# INA219-SOT23.net
KiCad netlist of a schematic drawn in EAGLE
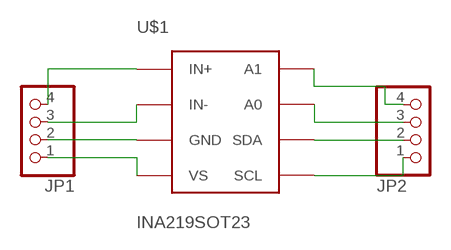
[diagram p0: schematic, sheet 1]

(export (version "E")
  (design (tool "Eeschema 10.0.6"))
  (components
    (comp (ref "JP1")
      (value "PINHD-1X4")
      (footprint "eagle-import:1X04")
      (libsource (lib "eagle-import") (part "PINHD-1X4"))
    )
    (comp (ref "JP2")
      (value "PINHD-1X4")
      (footprint "eagle-import:1X04")
      (libsource (lib "eagle-import") (part "PINHD-1X4"))
    )
    (comp (ref "U$1")
      (value "INA219SOT23")
      (footprint "eagle-import:SOT-23-8")
      (libsource (lib "eagle-import") (part "INA219SOT23"))
    )
  )
  (nets
    (net (code "1") (name "Net-(U$1-A0)") (class "Default")
      (node (ref "JP2") (pin "3") (pinfunction "3_3") (pintype "passive"))
      (node (ref "U$1") (pin "P$7") (pinfunction "A0_P$7") (pintype "bidirectional"))
    )
    (net (code "2") (name "Net-(U$1-A1)") (class "Default")
      (node (ref "JP2") (pin "4") (pinfunction "4_4") (pintype "passive"))
      (node (ref "U$1") (pin "P$8") (pinfunction "A1_P$8") (pintype "bidirectional"))
    )
    (net (code "3") (name "Net-(U$1-GND)") (class "Default")
      (node (ref "JP1") (pin "2") (pinfunction "2_2") (pintype "passive"))
      (node (ref "U$1") (pin "P$3") (pinfunction "GND_P$3") (pintype "bidirectional"))
    )
    (net (code "4") (name "Net-(U$1-IN+)") (class "Default")
      (node (ref "JP1") (pin "4") (pinfunction "4_4") (pintype "passive"))
      (node (ref "U$1") (pin "P$1") (pinfunction "IN+_P$1") (pintype "bidirectional"))
    )
    (net (code "5") (name "Net-(U$1-IN-)") (class "Default")
      (node (ref "JP1") (pin "3") (pinfunction "3_3") (pintype "passive"))
      (node (ref "U$1") (pin "P$2") (pinfunction "IN-_P$2") (pintype "bidirectional"))
    )
    (net (code "6") (name "Net-(U$1-SCL)") (class "Default")
      (node (ref "JP2") (pin "1") (pinfunction "1_1") (pintype "passive"))
      (node (ref "U$1") (pin "P$5") (pinfunction "SCL_P$5") (pintype "bidirectional"))
    )
    (net (code "7") (name "Net-(U$1-SDA)") (class "Default")
      (node (ref "JP2") (pin "2") (pinfunction "2_2") (pintype "passive"))
      (node (ref "U$1") (pin "P$6") (pinfunction "SDA_P$6") (pintype "bidirectional"))
    )
    (net (code "8") (name "Net-(U$1-VS)") (class "Default")
      (node (ref "JP1") (pin "1") (pinfunction "1_1") (pintype "passive"))
      (node (ref "U$1") (pin "P$4") (pinfunction "VS_P$4") (pintype "bidirectional"))
    )
  )
)
